# rapidshark-half-assed-bldc-esc-mk-1_0.net
KiCad netlist of a schematic drawn in EAGLE
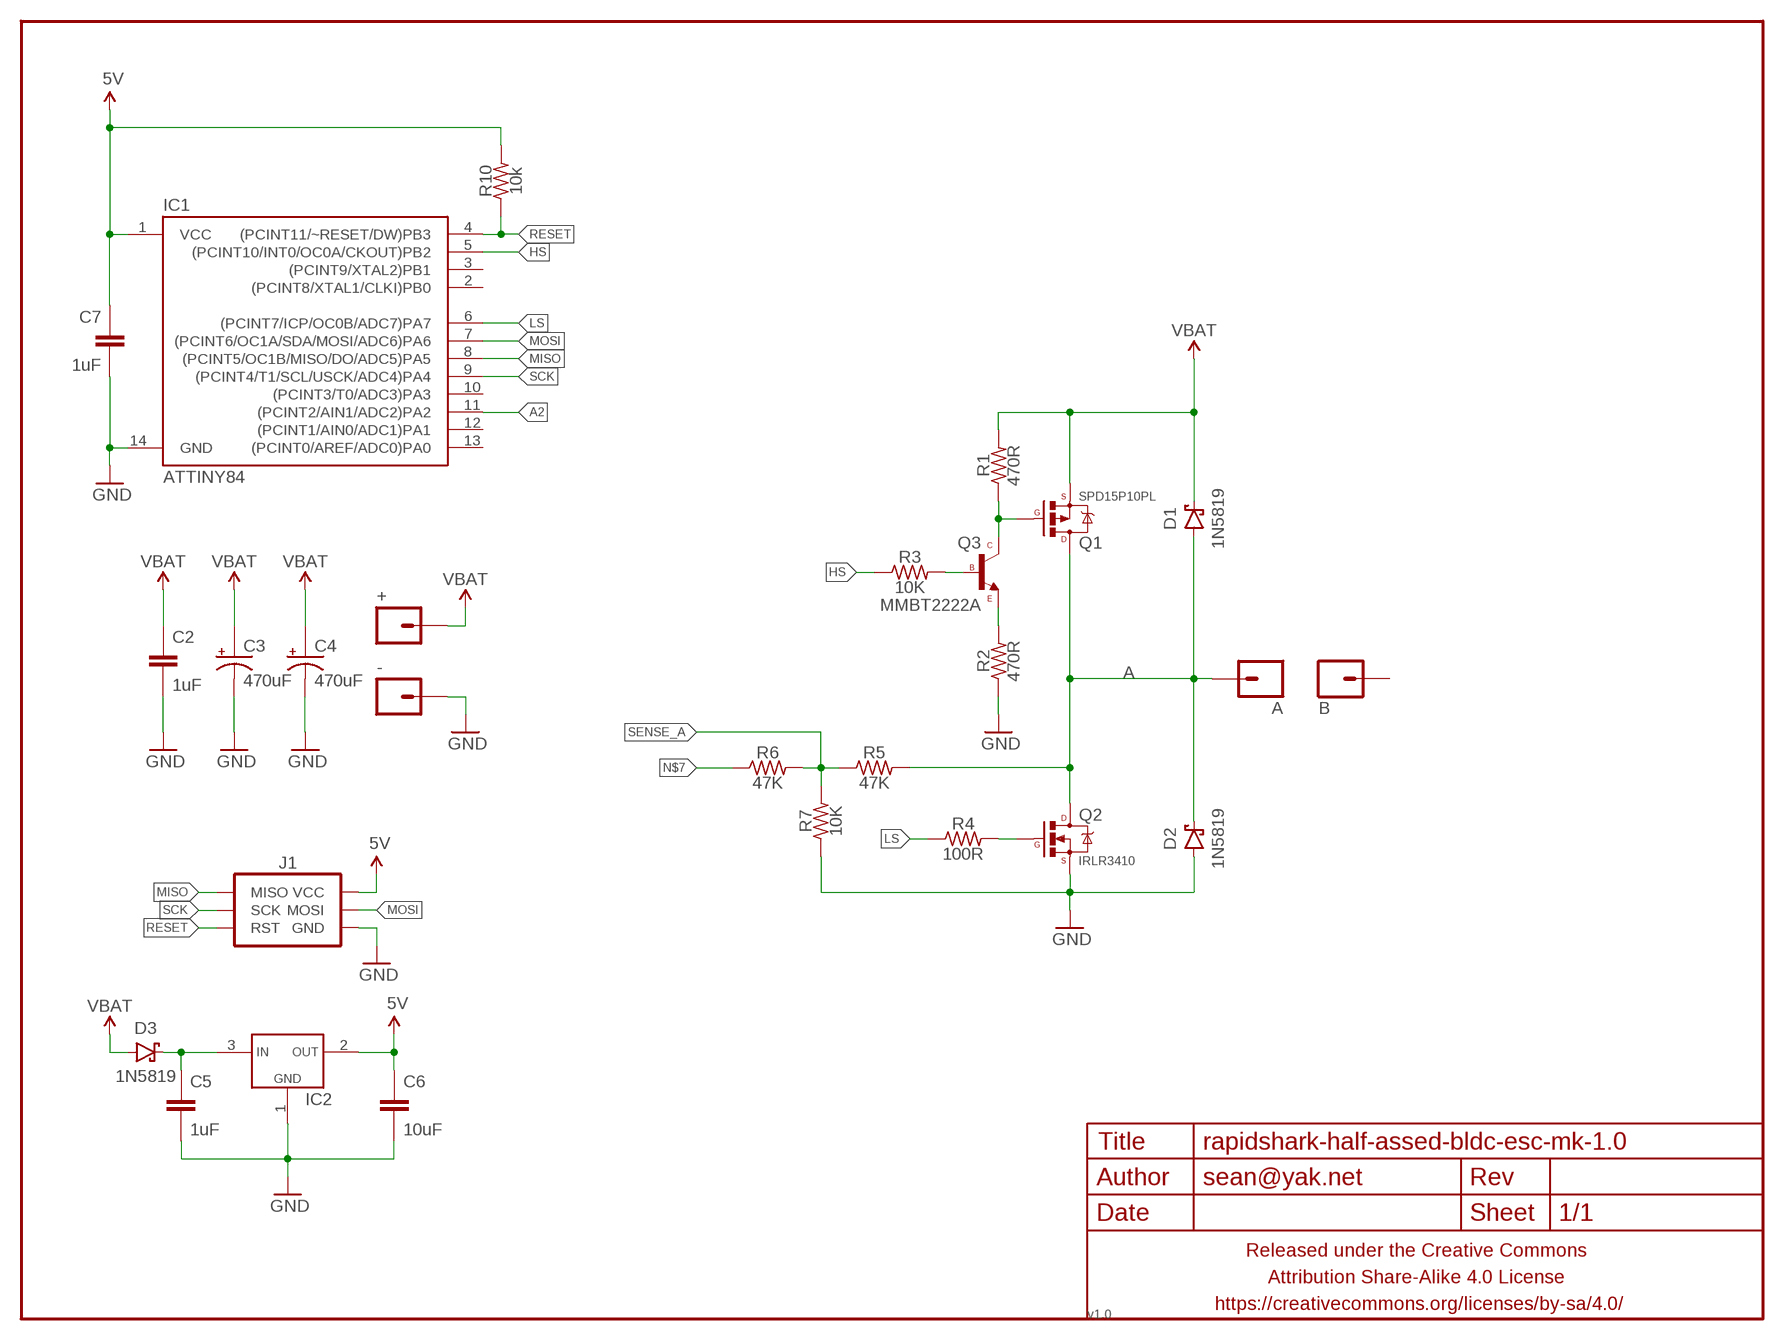
[diagram p0: schematic, sheet 1]

(export (version "E")
  (design (tool "Eeschema 10.0.6"))
  (components
    (comp (ref "+")
      (value "M01PTH-1.4MM")
      (footprint "eagle-import:1X01-1.4MM-CIR")
      (libsource (lib "eagle-import") (part "M01PTH-1.4MM"))
    )
    (comp (ref "-")
      (value "M01PTH-1.4MM")
      (footprint "eagle-import:1X01-1.4MM-CIR")
      (libsource (lib "eagle-import") (part "M01PTH-1.4MM"))
    )
    (comp (ref "A")
      (value "M01PTH-1.4MM")
      (footprint "eagle-import:1X01-1.4MM-CIR")
      (libsource (lib "eagle-import") (part "M01PTH-1.4MM"))
    )
    (comp (ref "B")
      (value "M01PTH-1.4MM")
      (footprint "eagle-import:1X01-1.4MM-CIR")
      (libsource (lib "eagle-import") (part "M01PTH-1.4MM"))
    )
    (comp (ref "C2")
      (value "1uF")
      (footprint "eagle-import:C0603-TIGHTER")
      (libsource (lib "eagle-import") (part "CAPACITOR-CERAMICC0603-TIGHTER"))
    )
    (comp (ref "C3")
      (value "470uF")
      (footprint "eagle-import:E5-10,5")
      (libsource (lib "eagle-import") (part "CAPACITOR-POLARIZEDE5-10.5"))
    )
    (comp (ref "C4")
      (value "470uF")
      (footprint "eagle-import:E5-10,5")
      (libsource (lib "eagle-import") (part "CAPACITOR-POLARIZEDE5-10.5"))
    )
    (comp (ref "C5")
      (value "1uF")
      (footprint "eagle-import:C0805-TIGHTER")
      (libsource (lib "eagle-import") (part "CAPACITOR-CERAMICC0805-TIGHTER"))
    )
    (comp (ref "C6")
      (value "10uF")
      (footprint "eagle-import:C0805-TIGHTER")
      (libsource (lib "eagle-import") (part "CAPACITOR-CERAMICC0805-TIGHTER"))
    )
    (comp (ref "C7")
      (value "1uF")
      (footprint "eagle-import:C0603-TIGHTER")
      (libsource (lib "eagle-import") (part "CAPACITOR-CERAMICC0603-TIGHTER"))
    )
    (comp (ref "D1")
      (value "1N5819")
      (footprint "eagle-import:SMA-DIODE-SCHOTTKY")
      (libsource (lib "eagle-import") (part "DIODE-SCHOTTKYSMA"))
    )
    (comp (ref "D2")
      (value "1N5819")
      (footprint "eagle-import:SMA-DIODE-SCHOTTKY")
      (libsource (lib "eagle-import") (part "DIODE-SCHOTTKYSMA"))
    )
    (comp (ref "D3")
      (value "1N5819")
      (footprint "eagle-import:SOD323-SCHOTTKY")
      (libsource (lib "eagle-import") (part "DIODE-SCHOTTKYSOD323"))
    )
    (comp (ref "FRAME1")
      (value "FRAME-LETTERNO_PACKAGE")
      (footprint "eagle-import:DUMMY")
      (fields
        (field (name "DESIGNER") "sean@yak.net")
        (field (name "VERSION") "v1.0")
        (field (name "VERSION_1") "v1.0")
      )
      (libsource (lib "eagle-import") (part "FRAME-LETTERNO_PACKAGE"))
    )
    (comp (ref "IC1")
      (value "ATTINY84")
      (footprint "eagle-import:SO14")
      (libsource (lib "eagle-import") (part "ATTINY84"))
    )
    (comp (ref "IC2")
      (value "VREG_1117SOT-23")
      (footprint "eagle-import:SOT23")
      (libsource (lib "eagle-import") (part "VREG_1117SOT-23"))
    )
    (comp (ref "J1")
      (value "AVR_SPI_PRG_6INLINE")
      (footprint "eagle-import:AVR_MINI_PROG")
      (libsource (lib "eagle-import") (part "AVR_SPI_PRG_6INLINE"))
    )
    (comp (ref "Q1")
      (value "SPD15P10PL")
      (footprint "eagle-import:DPAK")
      (libsource (lib "eagle-import") (part "MOSFET-PCHANNELDPAK"))
    )
    (comp (ref "Q2")
      (value "IRLR3410")
      (footprint "eagle-import:DPAK")
      (libsource (lib "eagle-import") (part "MOSFET-NCHANNELFDD8780"))
    )
    (comp (ref "Q3")
      (value "MMBT2222A")
      (footprint "eagle-import:SOT23")
      (libsource (lib "eagle-import") (part "TRANSISTOR_NPNMMBT2222A"))
    )
    (comp (ref "R1")
      (value "470R")
      (footprint "eagle-import:R0603-TIGHTER")
      (libsource (lib "eagle-import") (part "RESISTORR0603-TIGHTER"))
    )
    (comp (ref "R2")
      (value "470R")
      (footprint "eagle-import:R0603-TIGHTER")
      (libsource (lib "eagle-import") (part "RESISTORR0603-TIGHTER"))
    )
    (comp (ref "R3")
      (value "10K")
      (footprint "eagle-import:R0603-TIGHTER")
      (libsource (lib "eagle-import") (part "RESISTORR0603-TIGHTER"))
    )
    (comp (ref "R4")
      (value "100R")
      (footprint "eagle-import:R0603-TIGHTER")
      (libsource (lib "eagle-import") (part "RESISTORR0603-TIGHTER"))
    )
    (comp (ref "R5")
      (value "47K")
      (footprint "eagle-import:R0603-TIGHTER")
      (libsource (lib "eagle-import") (part "RESISTORR0603-TIGHTER"))
    )
    (comp (ref "R6")
      (value "47K")
      (footprint "eagle-import:R0603-TIGHTER")
      (libsource (lib "eagle-import") (part "RESISTORR0603-TIGHTER"))
    )
    (comp (ref "R7")
      (value "10K")
      (footprint "eagle-import:R0603-TIGHTER")
      (libsource (lib "eagle-import") (part "RESISTORR0603-TIGHTER"))
    )
    (comp (ref "R10")
      (value "10k")
      (footprint "eagle-import:R0603-TIGHTER")
      (libsource (lib "eagle-import") (part "RESISTORR0603-TIGHTER"))
    )
  )
  (nets
    (net (code "1") (name "/A") (class "Default")
      (node (ref "A") (pin "P$1") (pinfunction "1_P$1") (pintype "passive"))
      (node (ref "D1") (pin "A") (pinfunction "A_A") (pintype "passive"))
      (node (ref "D2") (pin "C") (pinfunction "C_C") (pintype "passive"))
      (node (ref "Q1") (pin "4") (pinfunction "D_4") (pintype "passive"))
      (node (ref "Q2") (pin "4") (pinfunction "D_4") (pintype "passive"))
      (node (ref "R5") (pin "2") (pinfunction "2_2") (pintype "passive"))
    )
    (net (code "2") (name "5V") (class "Default")
      (node (ref "C6") (pin "1") (pinfunction "1_1") (pintype "passive"))
      (node (ref "C7") (pin "1") (pinfunction "1_1") (pintype "passive"))
      (node (ref "IC1") (pin "1") (pinfunction "VCC_1") (pintype "bidirectional"))
      (node (ref "IC2") (pin "2") (pinfunction "VOUT_2") (pintype "bidirectional"))
      (node (ref "J1") (pin "2") (pinfunction "VCC_2") (pintype "passive"))
      (node (ref "R10") (pin "2") (pinfunction "2_2") (pintype "passive"))
    )
    (net (code "3") (name "A2") (class "Default")
      (node (ref "IC1") (pin "11") (pinfunction "(PCINT2/AIN1/ADC2)PA2_11") (pintype "bidirectional"))
    )
    (net (code "4") (name "GND") (class "Default")
      (node (ref "-") (pin "P$1") (pinfunction "1_P$1") (pintype "passive"))
      (node (ref "C2") (pin "2") (pinfunction "2_2") (pintype "passive"))
      (node (ref "C3") (pin "-") (pinfunction "-_-") (pintype "passive"))
      (node (ref "C4") (pin "-") (pinfunction "-_-") (pintype "passive"))
      (node (ref "C5") (pin "2") (pinfunction "2_2") (pintype "passive"))
      (node (ref "C6") (pin "2") (pinfunction "2_2") (pintype "passive"))
      (node (ref "C7") (pin "2") (pinfunction "2_2") (pintype "passive"))
      (node (ref "D2") (pin "A") (pinfunction "A_A") (pintype "passive"))
      (node (ref "IC1") (pin "14") (pinfunction "GND_14") (pintype "bidirectional"))
      (node (ref "IC2") (pin "1") (pinfunction "GND_1") (pintype "bidirectional"))
      (node (ref "J1") (pin "6") (pinfunction "GND_6") (pintype "passive"))
      (node (ref "Q2") (pin "3") (pinfunction "S_3") (pintype "passive"))
      (node (ref "R2") (pin "1") (pinfunction "1_1") (pintype "passive"))
      (node (ref "R7") (pin "1") (pinfunction "1_1") (pintype "passive"))
    )
    (net (code "5") (name "HS") (class "Default")
      (node (ref "IC1") (pin "5") (pinfunction "(PCINT10/INT0/OC0A/CKOUT)PB2_5") (pintype "bidirectional"))
      (node (ref "R3") (pin "1") (pinfunction "1_1") (pintype "passive"))
    )
    (net (code "6") (name "LS") (class "Default")
      (node (ref "IC1") (pin "6") (pinfunction "(PCINT7/ICP/OC0B/ADC7)PA7_6") (pintype "bidirectional"))
      (node (ref "R4") (pin "1") (pinfunction "1_1") (pintype "passive"))
    )
    (net (code "7") (name "MISO") (class "Default")
      (node (ref "IC1") (pin "8") (pinfunction "(PCINT5/OC1B/MISO/DO/ADC5)PA5_8") (pintype "bidirectional"))
      (node (ref "J1") (pin "1") (pinfunction "MISO_1") (pintype "passive"))
    )
    (net (code "8") (name "MOSI") (class "Default")
      (node (ref "IC1") (pin "7") (pinfunction "(PCINT6/OC1A/SDA/MOSI/ADC6)PA6_7") (pintype "bidirectional"))
      (node (ref "J1") (pin "4") (pinfunction "MOSI_4") (pintype "passive"))
    )
    (net (code "9") (name "N$7") (class "Default")
      (node (ref "R6") (pin "1") (pinfunction "1_1") (pintype "passive"))
    )
    (net (code "10") (name "Net-(IC2-VIN)") (class "Default")
      (node (ref "C5") (pin "1") (pinfunction "1_1") (pintype "passive"))
      (node (ref "D3") (pin "C") (pinfunction "C_C") (pintype "passive"))
      (node (ref "IC2") (pin "3") (pinfunction "VIN_3") (pintype "bidirectional"))
    )
    (net (code "11") (name "Net-(Q1-G)") (class "Default")
      (node (ref "Q1") (pin "1") (pinfunction "G_1") (pintype "passive"))
      (node (ref "Q3") (pin "3") (pinfunction "C_3") (pintype "passive"))
      (node (ref "R1") (pin "1") (pinfunction "1_1") (pintype "passive"))
    )
    (net (code "12") (name "Net-(Q2-G)") (class "Default")
      (node (ref "Q2") (pin "1") (pinfunction "G_1") (pintype "passive"))
      (node (ref "R4") (pin "2") (pinfunction "2_2") (pintype "passive"))
    )
    (net (code "13") (name "Net-(Q3-B)") (class "Default")
      (node (ref "Q3") (pin "1") (pinfunction "B_1") (pintype "passive"))
      (node (ref "R3") (pin "2") (pinfunction "2_2") (pintype "passive"))
    )
    (net (code "14") (name "Net-(Q3-E)") (class "Default")
      (node (ref "Q3") (pin "2") (pinfunction "E_2") (pintype "passive"))
      (node (ref "R2") (pin "2") (pinfunction "2_2") (pintype "passive"))
    )
    (net (code "15") (name "RESET") (class "Default")
      (node (ref "IC1") (pin "4") (pinfunction "(PCINT11/~{RESET/DW})PB3_4") (pintype "bidirectional"))
      (node (ref "J1") (pin "5") (pinfunction "RST_5") (pintype "passive"))
      (node (ref "R10") (pin "1") (pinfunction "1_1") (pintype "passive"))
    )
    (net (code "16") (name "SCK") (class "Default")
      (node (ref "IC1") (pin "9") (pinfunction "(PCINT4/T1/SCL/USCK/ADC4)PA4_9") (pintype "bidirectional"))
      (node (ref "J1") (pin "3") (pinfunction "SCK_3") (pintype "passive"))
    )
    (net (code "17") (name "SENSE_A") (class "Default")
      (node (ref "R5") (pin "1") (pinfunction "1_1") (pintype "passive"))
      (node (ref "R6") (pin "2") (pinfunction "2_2") (pintype "passive"))
      (node (ref "R7") (pin "2") (pinfunction "2_2") (pintype "passive"))
    )
    (net (code "18") (name "VBAT") (class "Default")
      (node (ref "+") (pin "P$1") (pinfunction "1_P$1") (pintype "passive"))
      (node (ref "C2") (pin "1") (pinfunction "1_1") (pintype "passive"))
      (node (ref "C3") (pin "+") (pinfunction "+_+") (pintype "passive"))
      (node (ref "C4") (pin "+") (pinfunction "+_+") (pintype "passive"))
      (node (ref "D1") (pin "C") (pinfunction "C_C") (pintype "passive"))
      (node (ref "D3") (pin "A") (pinfunction "A_A") (pintype "passive"))
      (node (ref "Q1") (pin "3") (pinfunction "S_3") (pintype "passive"))
      (node (ref "R1") (pin "2") (pinfunction "2_2") (pintype "passive"))
    )
    (net (code "19") (name "unconnected-(B-1-PadP$1)") (class "Default")
      (node (ref "B") (pin "P$1") (pinfunction "1_P$1") (pintype "passive"))
    )
    (net (code "20") (name "unconnected-(IC1-(PCINT0{slash}AREF{slash}ADC0)PA0-Pad13)") (class "Default")
      (node (ref "IC1") (pin "13") (pinfunction "(PCINT0/AREF/ADC0)PA0_13") (pintype "bidirectional"))
    )
    (net (code "21") (name "unconnected-(IC1-(PCINT1{slash}AIN0{slash}ADC1)PA1-Pad12)") (class "Default")
      (node (ref "IC1") (pin "12") (pinfunction "(PCINT1/AIN0/ADC1)PA1_12") (pintype "bidirectional"))
    )
    (net (code "22") (name "unconnected-(IC1-(PCINT3{slash}T0{slash}ADC3)PA3-Pad10)") (class "Default")
      (node (ref "IC1") (pin "10") (pinfunction "(PCINT3/T0/ADC3)PA3_10") (pintype "bidirectional"))
    )
    (net (code "23") (name "unconnected-(IC1-(PCINT8{slash}XTAL1{slash}CLKI)PB0-Pad2)") (class "Default")
      (node (ref "IC1") (pin "2") (pinfunction "(PCINT8/XTAL1/CLKI)PB0_2") (pintype "bidirectional"))
    )
    (net (code "24") (name "unconnected-(IC1-(PCINT9{slash}XTAL2)PB1-Pad3)") (class "Default")
      (node (ref "IC1") (pin "3") (pinfunction "(PCINT9/XTAL2)PB1_3") (pintype "bidirectional"))
    )
  )
)
